# CAN_new.net
KiCad netlist of a schematic drawn in Altium Designer
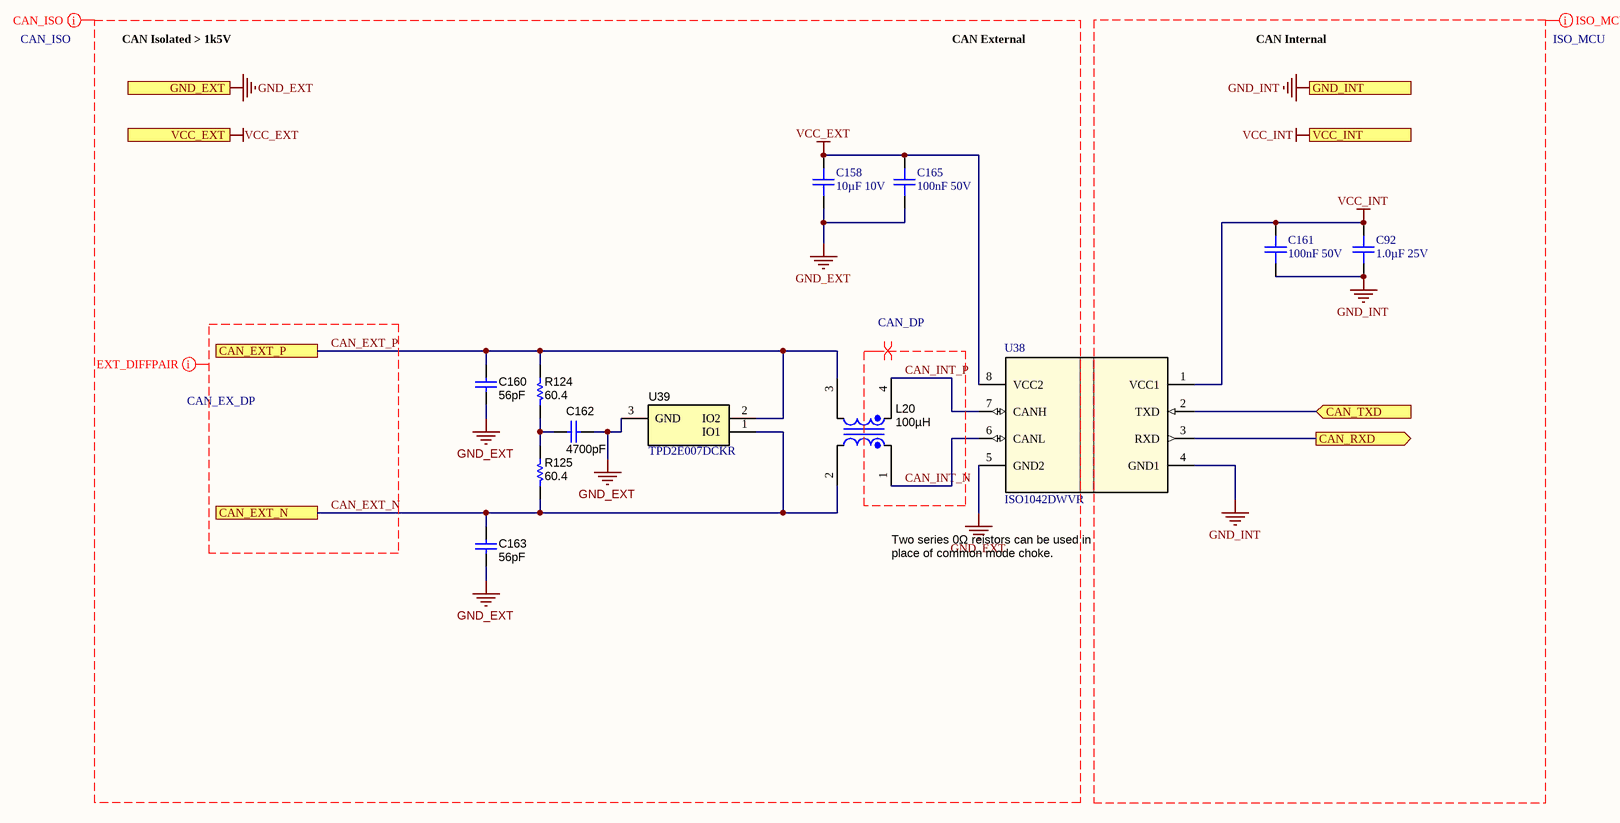
[diagram p0: CAN_new.SchDoc]

(export (version "E")
  (design (tool "Eeschema 10.0.6"))
  (components
    (comp (ref "C92")
      (value "1.0µF 25V")
      (footprint "0603C")
      (description "Ceramic, 1.0µF, ±10%, 25V, X7R, –55 to 125°C, 0603 (1608),RoHS, Automotive")
      (fields (field (name "PART NUMBER") "GCJ188R71E105KA01") (field (name "TOLERANCE") "±10%"))
      (libsource (lib "master-010106") (part "gen_C_ceramic_1u_25V_X7R_0603"))
    )
    (comp (ref "C158")
      (value "10µF 10V")
      (footprint "0805C")
      (description "Ceramic, 10µF, ±10%, 10V, X7R, –55 to 125°C, 0805 (2012),RoHS, Automotive")
      (fields (field (name "PART NUMBER") "GCJ21BR71A106KE01") (field (name "TOLERANCE") "±10%"))
      (libsource (lib "master-010106") (part "gen_C_ceramic_10u_10V_X7R_0805"))
    )
    (comp (ref "C160")
      (value "GRM1885C1H560JA01D")
      (footprint "0603C")
      (description "CAP, CERM, 56 pF, 50 V, +/- 5%, C0G/NP0, 0603")
      (fields
        (field (name "VALUEDISPLAYED") "56pF")
        (field (name "MANUFACTURER") "MuRata")
        (field (name "PUBLISHER") "Texas Instruments")
      )
      (libsource (lib "Capacitor_Ceramic") (part "GRM1885C1H560JA01D"))
    )
    (comp (ref "C161")
      (value "100nF 50V")
      (footprint "0603C")
      (description "Ceramic, 100nF, ±10%, 50V, X7R, –55 to 125°C, 0603 (1608),RoHS, Automotive")
      (fields (field (name "PART NUMBER") "GCJ188R71H104KA12") (field (name "TOLERANCE") "±10%"))
      (libsource (lib "master-010106") (part "C"))
    )
    (comp (ref "C162")
      (value "GCM188R71H472KA37D")
      (footprint "0603C")
      (description "CAP, CERM, 4700 pF, 50 V, +/- 10%, X7R, AEC-Q200 Grade 1, 0603")
      (fields
        (field (name "VALUEDISPLAYED") "4700pF")
        (field (name "MANUFACTURER") "MuRata")
        (field (name "PUBLISHER") "Texas Instruments")
      )
      (libsource (lib "Capacitor_Ceramic") (part "GCM188R71H472KA37D"))
    )
    (comp (ref "C163")
      (value "GRM1885C1H560JA01D")
      (footprint "0603C")
      (description "CAP, CERM, 56 pF, 50 V, +/- 5%, C0G/NP0, 0603")
      (fields
        (field (name "VALUEDISPLAYED") "56pF")
        (field (name "MANUFACTURER") "MuRata")
        (field (name "PUBLISHER") "Texas Instruments")
      )
      (libsource (lib "Capacitor_Ceramic") (part "GRM1885C1H560JA01D"))
    )
    (comp (ref "C165")
      (value "100nF 50V")
      (footprint "0603C")
      (description "Ceramic, 100nF, ±10%, 50V, X7R, –55 to 125°C, 0603 (1608),RoHS, Automotive")
      (fields (field (name "PART NUMBER") "GCJ188R71H104KA12") (field (name "TOLERANCE") "±10%"))
      (libsource (lib "master-010106") (part "C"))
    )
    (comp (ref "L20")
      (value "B82789C0104H001")
      (footprint "SIMDAD_1812")
      (description "Coupled inductor, 100 µH, 0.15 A, 1.5 ohm, SMD")
      (fields
        (field (name "VALUEDISPLAYED") "100µH")
        (field (name "MANUFACTURER") "TDK")
        (field (name "SYMBOLCREATOR") "a0412235")
        (field (name "PUBLISHER") "Texas Instruments")
      )
      (libsource (lib "Coupled_Inductors") (part "B82789C0104H001"))
    )
    (comp (ref "R124")
      (value "CRCW120660R4FKEA")
      (footprint "1206R")
      (description "RES, 60.4, 1%, 0.25 W, 1206")
      (fields
        (field (name "VALUEDISPLAYED") "60.4")
        (field (name "MANUFACTURER") "Vishay-Dale")
        (field (name "PUBLISHER") "Texas Instruments")
      )
      (libsource (lib "Resistor_1206") (part "CRCW120660R4FKEA"))
    )
    (comp (ref "R125")
      (value "CRCW120660R4FKEA")
      (footprint "1206R")
      (description "RES, 60.4, 1%, 0.25 W, 1206")
      (fields
        (field (name "VALUEDISPLAYED") "60.4")
        (field (name "MANUFACTURER") "Vishay-Dale")
        (field (name "PUBLISHER") "Texas Instruments")
      )
      (libsource (lib "Resistor_1206") (part "CRCW120660R4FKEA"))
    )
    (comp (ref "U38")
      (value "ISO1042DWVR")
      (footprint "DWV0008A")
      (description "Imported")
      (fields (field (name "MANUFACTURER") "Texas Instruments"))
      (libsource (lib "ti-import") (part "ISO1042DWVR"))
    )
    (comp (ref "U39")
      (value "TPD2E007DCKR")
      (footprint "DCK0003A_N")
      (fields
        (field (name "MANUFACTURER") "Texas Instruments")
        (field (name "ALTERNATE PARTNUMBER") "Equivalent")
      )
      (libsource (lib "TI Interface ESD EMI Protection") (part "TPD2E007DCKR"))
    )
  )
  (nets
    (net (code "1") (name "/CAN_EXT_N") (class "Default")
      (node (ref "C163") (pin "1") (pinfunction "1_1") (pintype "passive"))
      (node (ref "L20") (pin "2") (pinfunction "2_2") (pintype "passive"))
      (node (ref "R125") (pin "1") (pinfunction "1_1") (pintype "passive"))
      (node (ref "U39") (pin "1") (pinfunction "IO1_1") (pintype "passive"))
    )
    (net (code "2") (name "/CAN_EXT_P") (class "Default")
      (node (ref "C160") (pin "1") (pinfunction "1_1") (pintype "passive"))
      (node (ref "L20") (pin "3") (pinfunction "3_3") (pintype "passive"))
      (node (ref "R124") (pin "2") (pinfunction "2_2") (pintype "passive"))
      (node (ref "U39") (pin "2") (pinfunction "IO2_2") (pintype "passive"))
    )
    (net (code "3") (name "/CAN_INT_N") (class "Default")
      (node (ref "L20") (pin "1") (pinfunction "1_1") (pintype "passive"))
      (node (ref "U38") (pin "6") (pinfunction "CANL_6") (pintype "bidirectional"))
    )
    (net (code "4") (name "/CAN_INT_P") (class "Default")
      (node (ref "L20") (pin "4") (pinfunction "4_4") (pintype "passive"))
      (node (ref "U38") (pin "7") (pinfunction "CANH_7") (pintype "bidirectional"))
    )
    (net (code "5") (name "/CAN_RXD") (class "Default")
      (node (ref "U38") (pin "3") (pinfunction "RXD_3") (pintype "output"))
    )
    (net (code "6") (name "/CAN_TXD") (class "Default")
      (node (ref "U38") (pin "2") (pinfunction "TXD_2") (pintype "input"))
    )
    (net (code "7") (name "GND_EXT") (class "Default")
      (node (ref "C158") (pin "2") (pinfunction "2_2") (pintype "passive"))
      (node (ref "C160") (pin "2") (pinfunction "2_2") (pintype "passive"))
      (node (ref "C162") (pin "2") (pinfunction "2_2") (pintype "passive"))
      (node (ref "C163") (pin "2") (pinfunction "2_2") (pintype "passive"))
      (node (ref "C165") (pin "1") (pinfunction "1_1") (pintype "passive"))
      (node (ref "U38") (pin "5") (pinfunction "GND2_5") (pintype "power_in"))
      (node (ref "U39") (pin "3") (pinfunction "GND_3") (pintype "power_in"))
    )
    (net (code "8") (name "GND_INT") (class "Default")
      (node (ref "C161") (pin "1") (pinfunction "1_1") (pintype "passive"))
      (node (ref "C92") (pin "1") (pinfunction "1_1") (pintype "passive"))
      (node (ref "U38") (pin "4") (pinfunction "GND1_4") (pintype "power_in"))
    )
    (net (code "9") (name "Net-(C162-Pad1)") (class "Default")
      (node (ref "C162") (pin "1") (pinfunction "1_1") (pintype "passive"))
      (node (ref "R124") (pin "1") (pinfunction "1_1") (pintype "passive"))
      (node (ref "R125") (pin "2") (pinfunction "2_2") (pintype "passive"))
    )
    (net (code "10") (name "VCC_EXT") (class "Default")
      (node (ref "C158") (pin "1") (pinfunction "1_1") (pintype "passive"))
      (node (ref "C165") (pin "2") (pinfunction "2_2") (pintype "passive"))
      (node (ref "U38") (pin "8") (pinfunction "VCC2_8") (pintype "power_in"))
    )
    (net (code "11") (name "VCC_INT") (class "Default")
      (node (ref "C161") (pin "2") (pinfunction "2_2") (pintype "passive"))
      (node (ref "C92") (pin "2") (pinfunction "2_2") (pintype "passive"))
      (node (ref "U38") (pin "1") (pinfunction "VCC1_1") (pintype "power_in"))
    )
  )
)
